# Walletv3.net
KiCad netlist of a schematic drawn in EAGLE
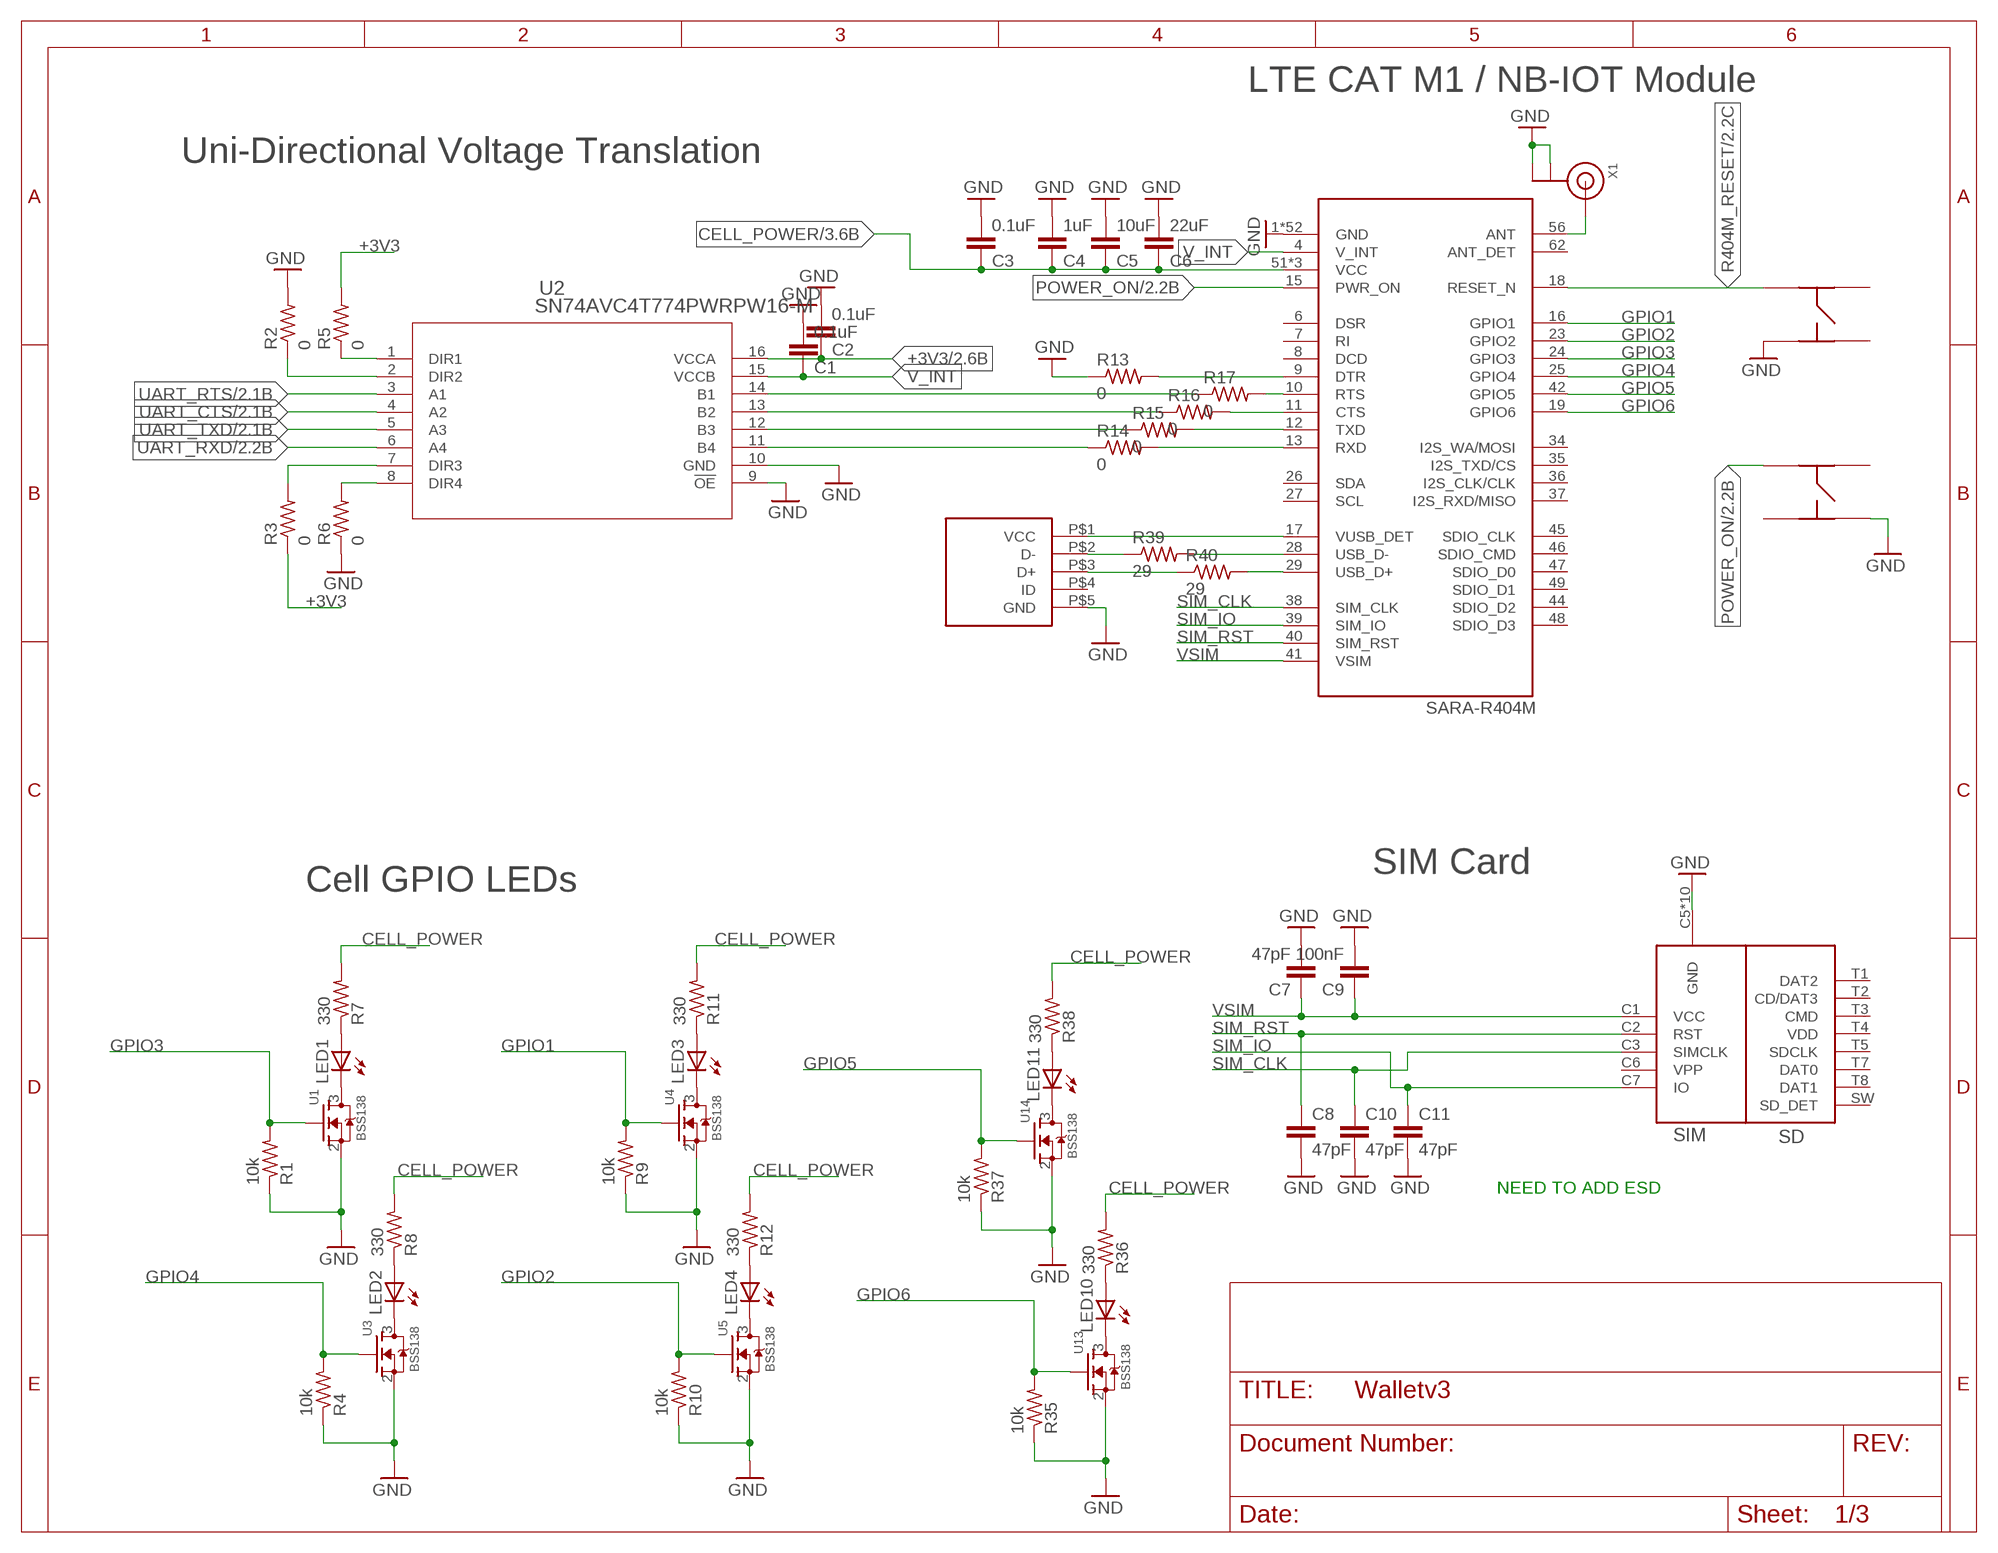
[diagram p0: schematic, sheet 1]
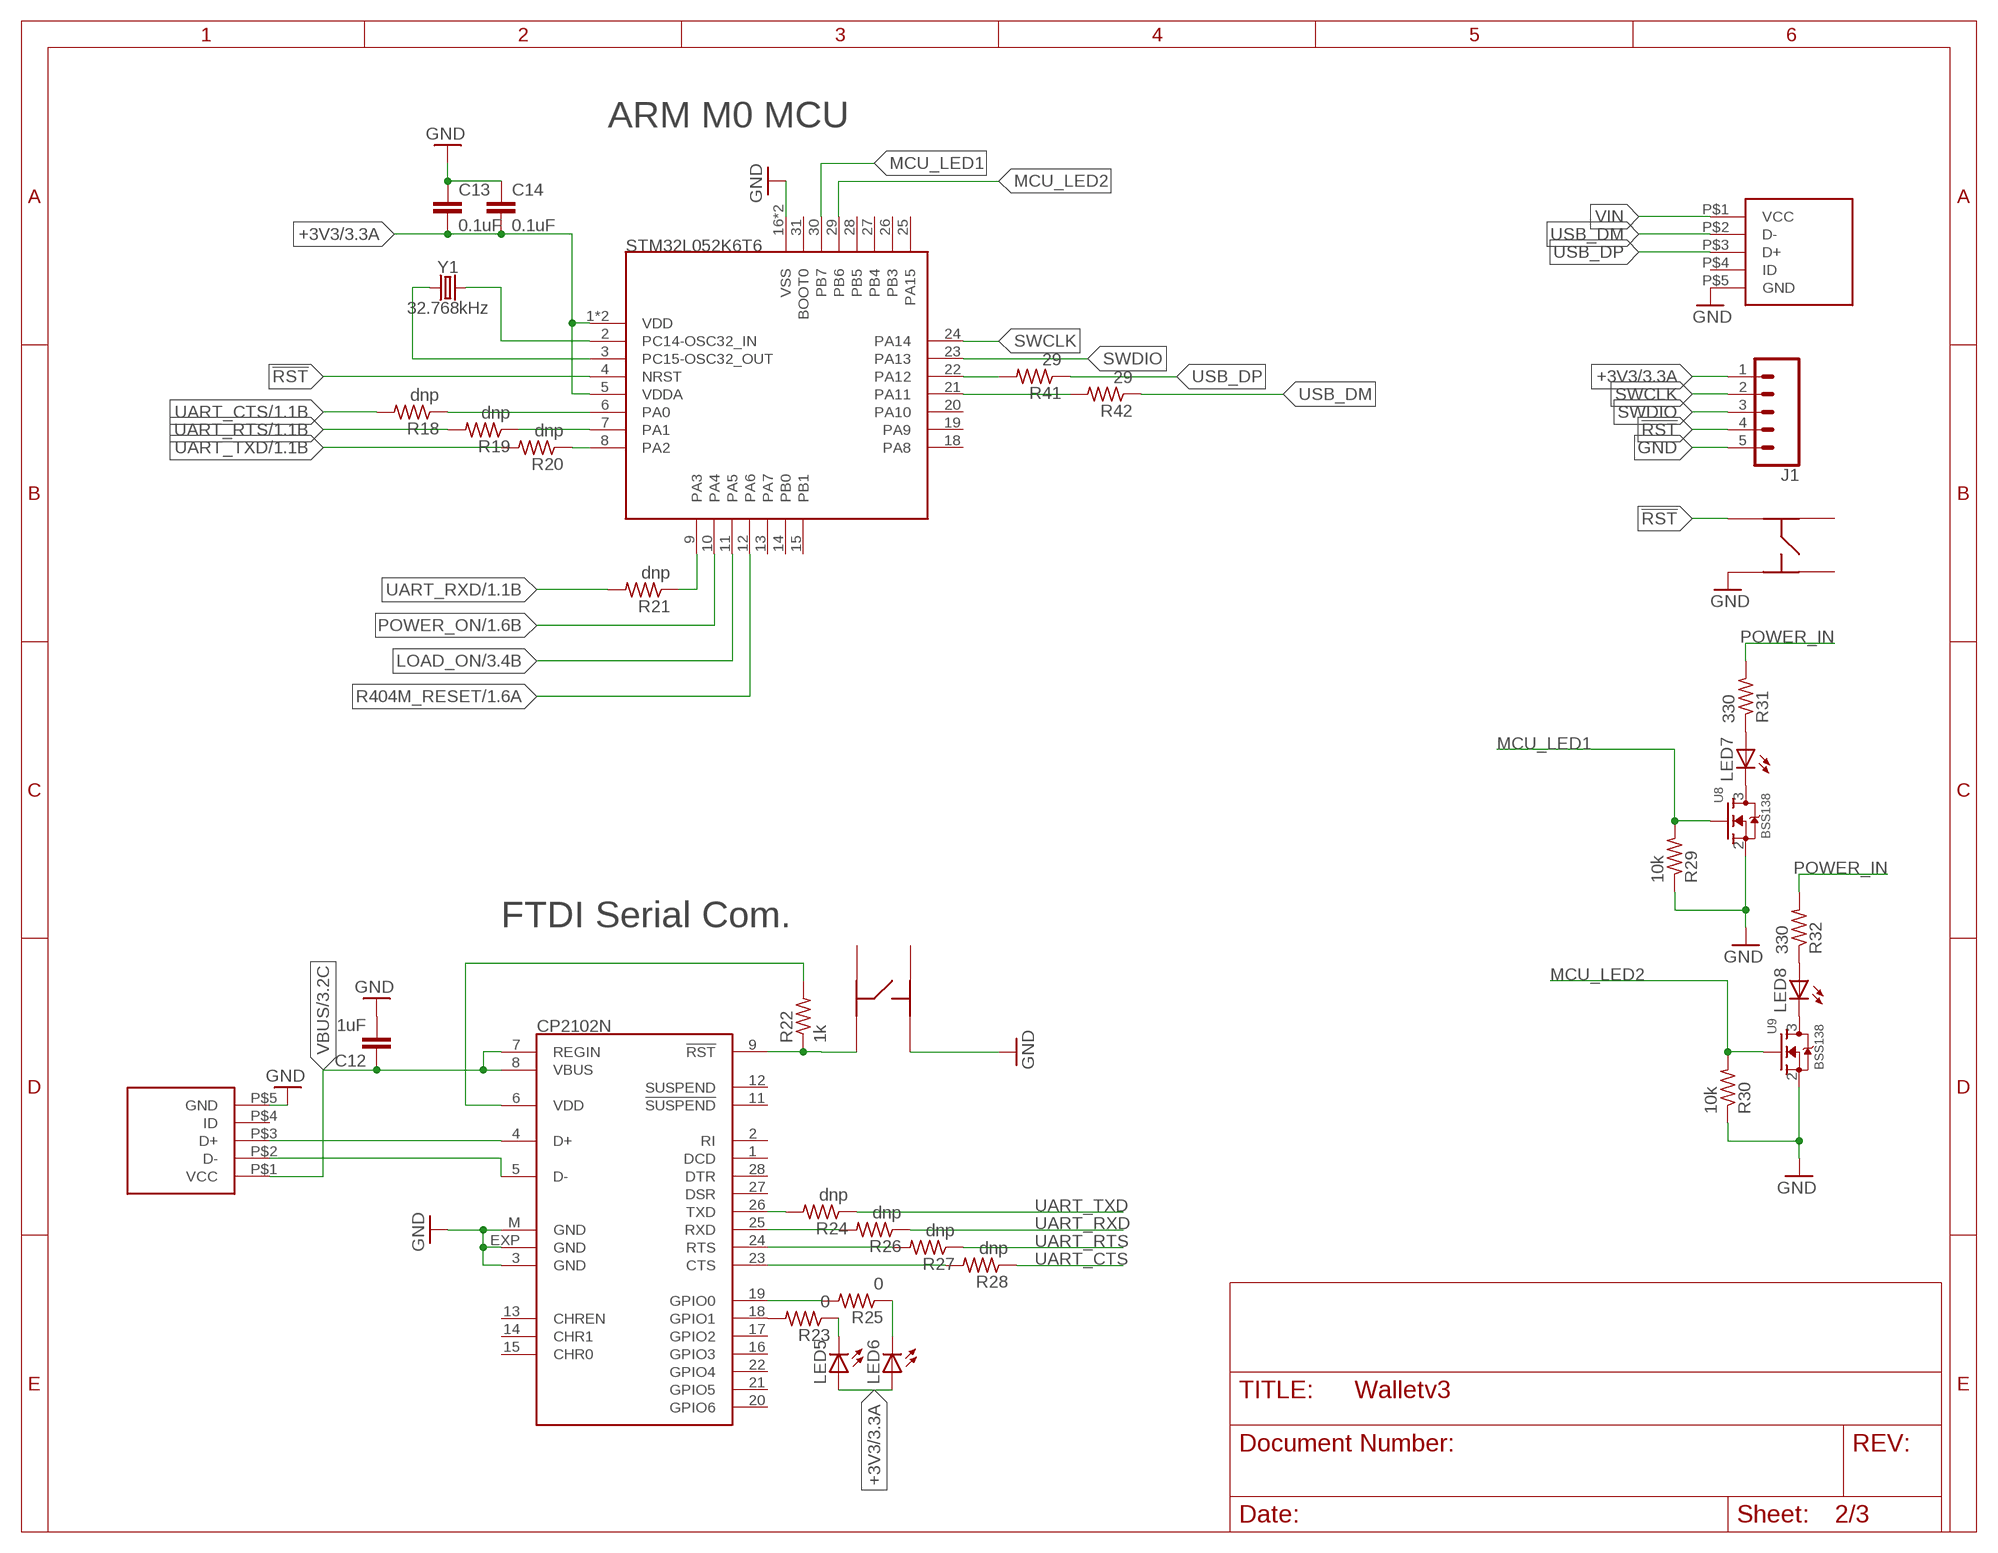
[diagram p1: schematic, sheet 2]
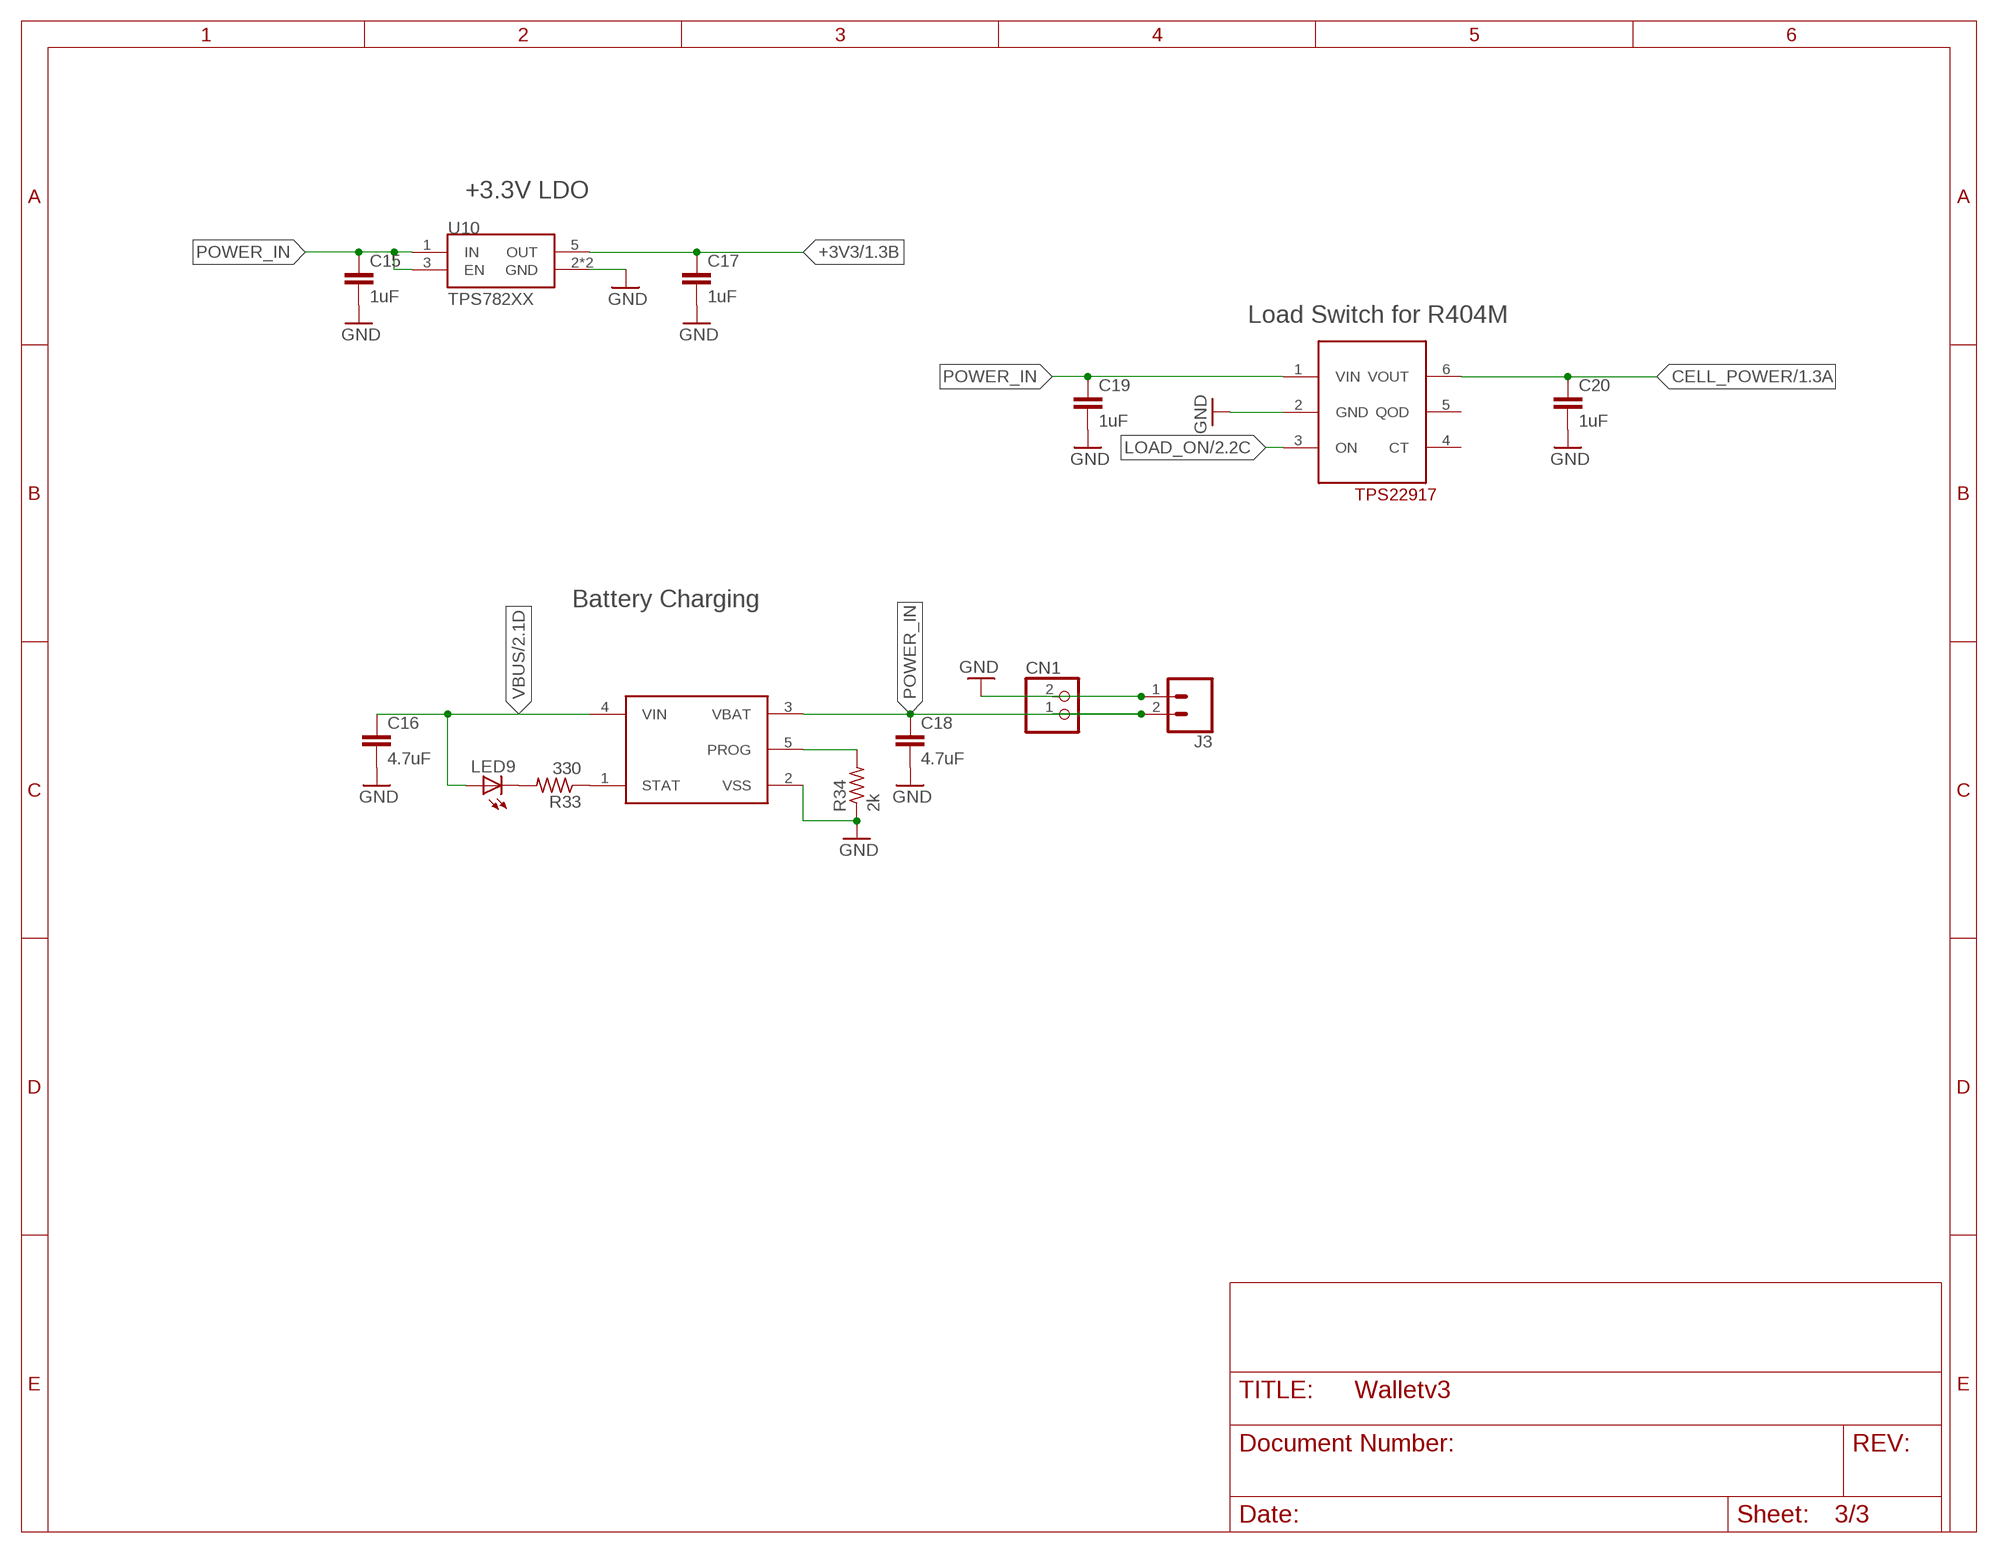
[diagram p2: schematic, sheet 3]

(export (version "E")
  (design (tool "Eeschema 10.0.6"))
  (components
    (comp (ref "C15")
      (value "1uF")
      (footprint "eagle-import:C0402")
      (libsource (lib "eagle-import") (part "C-EUC0402"))
    )
    (comp (ref "C16")
      (value "4.7uF")
      (footprint "eagle-import:C0603")
      (libsource (lib "eagle-import") (part "C-EUC0603"))
    )
    (comp (ref "C17")
      (value "1uF")
      (footprint "eagle-import:C0402")
      (libsource (lib "eagle-import") (part "C-EUC0402"))
    )
    (comp (ref "C18")
      (value "4.7uF")
      (footprint "eagle-import:C0603")
      (libsource (lib "eagle-import") (part "C-EUC0603"))
    )
    (comp (ref "C19")
      (value "1uF")
      (footprint "eagle-import:C0402")
      (libsource (lib "eagle-import") (part "C-EUC0402"))
    )
    (comp (ref "C20")
      (value "1uF")
      (footprint "eagle-import:C0402")
      (libsource (lib "eagle-import") (part "C-EUC0402"))
    )
    (comp (ref "CN1")
      (value "JST_2PIN-SMT-RA")
      (footprint "eagle-import:JST-PH-2-SMT-RA")
      (libsource (lib "eagle-import") (part "JST_2PIN-SMT-RA"))
    )
    (comp (ref "J3")
      (value "CONN_02")
      (footprint "eagle-import:1X02")
      (libsource (lib "eagle-import") (part "CONN_02"))
    )
    (comp (ref "LED9")
      (value "LEDCHIP-LED0603")
      (footprint "eagle-import:CHIP-LED0603")
      (libsource (lib "eagle-import") (part "LEDCHIP-LED0603"))
    )
    (comp (ref "R33")
      (value "330")
      (footprint "eagle-import:R0402")
      (libsource (lib "eagle-import") (part "R-US_R0402"))
    )
    (comp (ref "R34")
      (value "2k")
      (footprint "eagle-import:R0402")
      (libsource (lib "eagle-import") (part "R-US_R0402"))
    )
    (comp (ref "U10")
      (value "TPS782XX")
      (footprint "eagle-import:SOT23-5L")
      (libsource (lib "eagle-import") (part "TPS782XX"))
    )
    (comp (ref "U11")
      (value "MCP73831")
      (footprint "eagle-import:SOT23-5L")
      (libsource (lib "eagle-import") (part "MCP73831"))
    )
    (comp (ref "U12")
      (value "TPS22917")
      (footprint "eagle-import:SOT23-6")
      (libsource (lib "eagle-import") (part "TPS22917"))
    )
    (comp (ref "C12")
      (value "1uF")
      (footprint "eagle-import:C0402")
      (libsource (lib "eagle-import") (part "C-EUC0402"))
    )
    (comp (ref "C13")
      (value "0.1uF")
      (footprint "eagle-import:C0402")
      (libsource (lib "eagle-import") (part "C-EUC0402"))
    )
    (comp (ref "C14")
      (value "0.1uF")
      (footprint "eagle-import:C0402")
      (libsource (lib "eagle-import") (part "C-EUC0402"))
    )
    (comp (ref "IC1")
      (value "CP2102")
      (footprint "eagle-import:MLP28")
      (fields (field (name "MF") "FARNELL") (field (name "MPN") "CP2102-GM"))
      (libsource (lib "eagle-import") (part "CP2102"))
    )
    (comp (ref "J1")
      (value "CONN_05")
      (footprint "eagle-import:1X05")
      (libsource (lib "eagle-import") (part "CONN_05"))
    )
    (comp (ref "LED5")
      (value "LEDCHIPLED_0603")
      (footprint "eagle-import:CHIPLED_0603")
      (libsource (lib "eagle-import") (part "LEDCHIPLED_0603"))
    )
    (comp (ref "LED6")
      (value "LEDCHIPLED_0603")
      (footprint "eagle-import:CHIPLED_0603")
      (libsource (lib "eagle-import") (part "LEDCHIPLED_0603"))
    )
    (comp (ref "LED7")
      (value "LEDCHIPLED_0603")
      (footprint "eagle-import:CHIPLED_0603")
      (libsource (lib "eagle-import") (part "LEDCHIPLED_0603"))
    )
    (comp (ref "LED8")
      (value "LEDCHIPLED_0603")
      (footprint "eagle-import:CHIPLED_0603")
      (libsource (lib "eagle-import") (part "LEDCHIPLED_0603"))
    )
    (comp (ref "R18")
      (value "dnp")
      (footprint "eagle-import:R0402")
      (libsource (lib "eagle-import") (part "R-US_R0402"))
    )
    (comp (ref "R19")
      (value "dnp")
      (footprint "eagle-import:R0402")
      (libsource (lib "eagle-import") (part "R-US_R0402"))
    )
    (comp (ref "R20")
      (value "dnp")
      (footprint "eagle-import:R0402")
      (libsource (lib "eagle-import") (part "R-US_R0402"))
    )
    (comp (ref "R21")
      (value "dnp")
      (footprint "eagle-import:R0402")
      (libsource (lib "eagle-import") (part "R-US_R0402"))
    )
    (comp (ref "R22")
      (value "1k")
      (footprint "eagle-import:R0402")
      (libsource (lib "eagle-import") (part "R-US_R0402"))
    )
    (comp (ref "R23")
      (value "0")
      (footprint "eagle-import:R0402")
      (libsource (lib "eagle-import") (part "R-US_R0402"))
    )
    (comp (ref "R24")
      (value "dnp")
      (footprint "eagle-import:R0402")
      (libsource (lib "eagle-import") (part "R-US_R0402"))
    )
    (comp (ref "R25")
      (value "0")
      (footprint "eagle-import:R0402")
      (libsource (lib "eagle-import") (part "R-US_R0402"))
    )
    (comp (ref "R26")
      (value "dnp")
      (footprint "eagle-import:R0402")
      (libsource (lib "eagle-import") (part "R-US_R0402"))
    )
    (comp (ref "R27")
      (value "dnp")
      (footprint "eagle-import:R0402")
      (libsource (lib "eagle-import") (part "R-US_R0402"))
    )
    (comp (ref "R28")
      (value "dnp")
      (footprint "eagle-import:R0402")
      (libsource (lib "eagle-import") (part "R-US_R0402"))
    )
    (comp (ref "R29")
      (value "10k")
      (footprint "eagle-import:R0402")
      (libsource (lib "eagle-import") (part "R-US_R0402"))
    )
    (comp (ref "R30")
      (value "10k")
      (footprint "eagle-import:R0402")
      (libsource (lib "eagle-import") (part "R-US_R0402"))
    )
    (comp (ref "R31")
      (value "330")
      (footprint "eagle-import:R0402")
      (libsource (lib "eagle-import") (part "R-US_R0402"))
    )
    (comp (ref "R32")
      (value "330")
      (footprint "eagle-import:R0402")
      (libsource (lib "eagle-import") (part "R-US_R0402"))
    )
    (comp (ref "R41")
      (value "29")
      (footprint "eagle-import:R0402")
      (libsource (lib "eagle-import") (part "R-US_R0402"))
    )
    (comp (ref "R42")
      (value "29")
      (footprint "eagle-import:R0402")
      (libsource (lib "eagle-import") (part "R-US_R0402"))
    )
    (comp (ref "S3")
      (value "KMR731NG")
      (footprint "eagle-import:KMR731NG")
      (libsource (lib "eagle-import") (part "KMR731NG"))
    )
    (comp (ref "S4")
      (value "KMR731NG")
      (footprint "eagle-import:KMR731NG")
      (libsource (lib "eagle-import") (part "KMR731NG"))
    )
    (comp (ref "U$3")
      (value "MICRO_USB")
      (footprint "eagle-import:MOLEX_USB")
      (libsource (lib "eagle-import") (part "MICRO_USB"))
    )
    (comp (ref "U$4")
      (value "MICRO_USB")
      (footprint "eagle-import:MOLEX_USB")
      (libsource (lib "eagle-import") (part "MICRO_USB"))
    )
    (comp (ref "U7")
      (value "STM32L052K6T6LQFP32-7X7")
      (footprint "eagle-import:QFP80P900X900X160-32")
      (libsource (lib "eagle-import") (part "STM32L052K6T6LQFP32-7X7"))
    )
    (comp (ref "U8")
      (value "BSS138")
      (footprint "eagle-import:SOT23-3")
      (libsource (lib "eagle-import") (part "BSS138"))
    )
    (comp (ref "U9")
      (value "BSS138")
      (footprint "eagle-import:SOT23-3")
      (libsource (lib "eagle-import") (part "BSS138"))
    )
    (comp (ref "Y1")
      (value "32.768kHz")
      (footprint "eagle-import:CRYSTAL-SMD-3.2X1.5MM")
      (libsource (lib "eagle-import") (part "CRYSTAL-32.768KHZSMD-3.2X1.5"))
    )
    (comp (ref "C1")
      (value "0.1uF")
      (footprint "eagle-import:C0402")
      (libsource (lib "eagle-import") (part "C-EUC0402"))
    )
    (comp (ref "C2")
      (value "0.1uF")
      (footprint "eagle-import:C0402")
      (libsource (lib "eagle-import") (part "C-EUC0402"))
    )
    (comp (ref "C3")
      (value "0.1uF")
      (footprint "eagle-import:C0402")
      (libsource (lib "eagle-import") (part "C-EUC0402"))
    )
    (comp (ref "C4")
      (value "1uF")
      (footprint "eagle-import:C0402")
      (libsource (lib "eagle-import") (part "C-EUC0402"))
    )
    (comp (ref "C5")
      (value "10uF")
      (footprint "eagle-import:C0603")
      (libsource (lib "eagle-import") (part "C-EUC0603"))
    )
    (comp (ref "C6")
      (value "22uF")
      (footprint "eagle-import:C0805")
      (libsource (lib "eagle-import") (part "C-EUC0805"))
    )
    (comp (ref "C7")
      (value "47pF")
      (footprint "eagle-import:C0402")
      (libsource (lib "eagle-import") (part "C-EUC0402"))
    )
    (comp (ref "C8")
      (value "47pF")
      (footprint "eagle-import:C0402")
      (libsource (lib "eagle-import") (part "C-EUC0402"))
    )
    (comp (ref "C9")
      (value "100nF")
      (footprint "eagle-import:C0402")
      (libsource (lib "eagle-import") (part "C-EUC0402"))
    )
    (comp (ref "C10")
      (value "47pF")
      (footprint "eagle-import:C0402")
      (libsource (lib "eagle-import") (part "C-EUC0402"))
    )
    (comp (ref "C11")
      (value "47pF")
      (footprint "eagle-import:C0402")
      (libsource (lib "eagle-import") (part "C-EUC0402"))
    )
    (comp (ref "LED1")
      (value "LEDCHIPLED_0603")
      (footprint "eagle-import:CHIPLED_0603")
      (libsource (lib "eagle-import") (part "LEDCHIPLED_0603"))
    )
    (comp (ref "LED2")
      (value "LEDCHIPLED_0603")
      (footprint "eagle-import:CHIPLED_0603")
      (libsource (lib "eagle-import") (part "LEDCHIPLED_0603"))
    )
    (comp (ref "LED3")
      (value "LEDCHIPLED_0603")
      (footprint "eagle-import:CHIPLED_0603")
      (libsource (lib "eagle-import") (part "LEDCHIPLED_0603"))
    )
    (comp (ref "LED4")
      (value "LEDCHIPLED_0603")
      (footprint "eagle-import:CHIPLED_0603")
      (libsource (lib "eagle-import") (part "LEDCHIPLED_0603"))
    )
    (comp (ref "LED10")
      (value "LEDCHIPLED_0603")
      (footprint "eagle-import:CHIPLED_0603")
      (libsource (lib "eagle-import") (part "LEDCHIPLED_0603"))
    )
    (comp (ref "LED11")
      (value "LEDCHIPLED_0603")
      (footprint "eagle-import:CHIPLED_0603")
      (libsource (lib "eagle-import") (part "LEDCHIPLED_0603"))
    )
    (comp (ref "R1")
      (value "10k")
      (footprint "eagle-import:R0402")
      (libsource (lib "eagle-import") (part "R-US_R0402"))
    )
    (comp (ref "R2")
      (value "0")
      (footprint "eagle-import:R0402")
      (libsource (lib "eagle-import") (part "R-US_R0402"))
    )
    (comp (ref "R3")
      (value "0")
      (footprint "eagle-import:R0402")
      (libsource (lib "eagle-import") (part "R-US_R0402"))
    )
    (comp (ref "R4")
      (value "10k")
      (footprint "eagle-import:R0402")
      (libsource (lib "eagle-import") (part "R-US_R0402"))
    )
    (comp (ref "R5")
      (value "0")
      (footprint "eagle-import:R0402")
      (libsource (lib "eagle-import") (part "R-US_R0402"))
    )
    (comp (ref "R6")
      (value "0")
      (footprint "eagle-import:R0402")
      (libsource (lib "eagle-import") (part "R-US_R0402"))
    )
    (comp (ref "R7")
      (value "330")
      (footprint "eagle-import:R0402")
      (libsource (lib "eagle-import") (part "R-US_R0402"))
    )
    (comp (ref "R8")
      (value "330")
      (footprint "eagle-import:R0402")
      (libsource (lib "eagle-import") (part "R-US_R0402"))
    )
    (comp (ref "R9")
      (value "10k")
      (footprint "eagle-import:R0402")
      (libsource (lib "eagle-import") (part "R-US_R0402"))
    )
    (comp (ref "R10")
      (value "10k")
      (footprint "eagle-import:R0402")
      (libsource (lib "eagle-import") (part "R-US_R0402"))
    )
    (comp (ref "R11")
      (value "330")
      (footprint "eagle-import:R0402")
      (libsource (lib "eagle-import") (part "R-US_R0402"))
    )
    (comp (ref "R12")
      (value "330")
      (footprint "eagle-import:R0402")
      (libsource (lib "eagle-import") (part "R-US_R0402"))
    )
    (comp (ref "R13")
      (value "0")
      (footprint "eagle-import:R0402")
      (libsource (lib "eagle-import") (part "R-US_R0402"))
    )
    (comp (ref "R14")
      (value "0")
      (footprint "eagle-import:R0402")
      (libsource (lib "eagle-import") (part "R-US_R0402"))
    )
    (comp (ref "R15")
      (value "0")
      (footprint "eagle-import:R0402")
      (libsource (lib "eagle-import") (part "R-US_R0402"))
    )
    (comp (ref "R16")
      (value "0")
      (footprint "eagle-import:R0402")
      (libsource (lib "eagle-import") (part "R-US_R0402"))
    )
    (comp (ref "R17")
      (value "0")
      (footprint "eagle-import:R0402")
      (libsource (lib "eagle-import") (part "R-US_R0402"))
    )
    (comp (ref "R35")
      (value "10k")
      (footprint "eagle-import:R0402")
      (libsource (lib "eagle-import") (part "R-US_R0402"))
    )
    (comp (ref "R36")
      (value "330")
      (footprint "eagle-import:R0402")
      (libsource (lib "eagle-import") (part "R-US_R0402"))
    )
    (comp (ref "R37")
      (value "10k")
      (footprint "eagle-import:R0402")
      (libsource (lib "eagle-import") (part "R-US_R0402"))
    )
    (comp (ref "R38")
      (value "330")
      (footprint "eagle-import:R0402")
      (libsource (lib "eagle-import") (part "R-US_R0402"))
    )
    (comp (ref "R39")
      (value "29")
      (footprint "eagle-import:R0402")
      (libsource (lib "eagle-import") (part "R-US_R0402"))
    )
    (comp (ref "R40")
      (value "29")
      (footprint "eagle-import:R0402")
      (libsource (lib "eagle-import") (part "R-US_R0402"))
    )
    (comp (ref "S1")
      (value "KMR731NG")
      (footprint "eagle-import:KMR731NG")
      (libsource (lib "eagle-import") (part "KMR731NG"))
    )
    (comp (ref "S2")
      (value "KMR731NG")
      (footprint "eagle-import:KMR731NG")
      (libsource (lib "eagle-import") (part "KMR731NG"))
    )
    (comp (ref "U$1")
      (value "SIM_SD_MOLEX")
      (footprint "eagle-import:SIM_SD_MOLEX")
      (libsource (lib "eagle-import") (part "SIM_SD_MOLEX"))
    )
    (comp (ref "U$2")
      (value "MICRO_USB")
      (footprint "eagle-import:MOLEX_USB")
      (libsource (lib "eagle-import") (part "MICRO_USB"))
    )
    (comp (ref "U1")
      (value "BSS138")
      (footprint "eagle-import:SOT23-3")
      (libsource (lib "eagle-import") (part "BSS138"))
    )
    (comp (ref "U2")
      (value "SN74AVC4T774PWRPW16-M")
      (footprint "eagle-import:PW16-M")
      (fields (field (name "MANUFACTURER_PART_NUMBER") "SN74AVC4T774PWR"))
      (libsource (lib "eagle-import") (part "SN74AVC4T774PWRPW16-M"))
    )
    (comp (ref "U3")
      (value "BSS138")
      (footprint "eagle-import:SOT23-3")
      (libsource (lib "eagle-import") (part "BSS138"))
    )
    (comp (ref "U4")
      (value "BSS138")
      (footprint "eagle-import:SOT23-3")
      (libsource (lib "eagle-import") (part "BSS138"))
    )
    (comp (ref "U5")
      (value "BSS138")
      (footprint "eagle-import:SOT23-3")
      (libsource (lib "eagle-import") (part "BSS138"))
    )
    (comp (ref "U6")
      (value "SARA-R404M")
      (footprint "eagle-import:SARA-R404M")
      (libsource (lib "eagle-import") (part "SARA-R404M"))
    )
    (comp (ref "U13")
      (value "BSS138")
      (footprint "eagle-import:SOT23-3")
      (libsource (lib "eagle-import") (part "BSS138"))
    )
    (comp (ref "U14")
      (value "BSS138")
      (footprint "eagle-import:SOT23-3")
      (libsource (lib "eagle-import") (part "BSS138"))
    )
    (comp (ref "X1")
      (value "ANTENNA_U.FL")
      (footprint "eagle-import:U.FL")
      (libsource (lib "eagle-import") (part "ANTENNA_U.FL"))
    )
  )
  (nets
    (net (code "1") (name "+3V3") (class "Default")
      (node (ref "C13") (pin "2") (pinfunction "2_2") (pintype "passive"))
      (node (ref "C14") (pin "2") (pinfunction "2_2") (pintype "passive"))
      (node (ref "C17") (pin "1") (pinfunction "1_1") (pintype "passive"))
      (node (ref "C2") (pin "1") (pinfunction "1_1") (pintype "passive"))
      (node (ref "J1") (pin "1") (pinfunction "1_1") (pintype "passive"))
      (node (ref "LED5") (pin "A") (pinfunction "A_A") (pintype "passive"))
      (node (ref "LED6") (pin "A") (pinfunction "A_A") (pintype "passive"))
      (node (ref "R3") (pin "1") (pinfunction "1_1") (pintype "passive"))
      (node (ref "R5") (pin "2") (pinfunction "2_2") (pintype "passive"))
      (node (ref "U10") (pin "5") (pinfunction "OUT_5") (pintype "bidirectional"))
      (node (ref "U2") (pin "16") (pinfunction "VCCA_16") (pintype "power_in"))
      (node (ref "U7") (pin "1") (pinfunction "VDD_1") (pintype "bidirectional"))
      (node (ref "U7") (pin "17") (pinfunction "VDD_17") (pintype "bidirectional"))
      (node (ref "U7") (pin "5") (pinfunction "VDDA_5") (pintype "bidirectional"))
    )
    (net (code "2") (name "CELL_POWER") (class "Default")
      (node (ref "C20") (pin "1") (pinfunction "1_1") (pintype "passive"))
      (node (ref "C3") (pin "1") (pinfunction "1_1") (pintype "passive"))
      (node (ref "C4") (pin "1") (pinfunction "1_1") (pintype "passive"))
      (node (ref "C5") (pin "1") (pinfunction "1_1") (pintype "passive"))
      (node (ref "C6") (pin "1") (pinfunction "1_1") (pintype "passive"))
      (node (ref "R11") (pin "2") (pinfunction "2_2") (pintype "passive"))
      (node (ref "R12") (pin "2") (pinfunction "2_2") (pintype "passive"))
      (node (ref "R36") (pin "2") (pinfunction "2_2") (pintype "passive"))
      (node (ref "R38") (pin "2") (pinfunction "2_2") (pintype "passive"))
      (node (ref "R7") (pin "2") (pinfunction "2_2") (pintype "passive"))
      (node (ref "R8") (pin "2") (pinfunction "2_2") (pintype "passive"))
      (node (ref "U12") (pin "6") (pinfunction "VOUT_6") (pintype "bidirectional"))
      (node (ref "U6") (pin "51") (pinfunction "VCC_51") (pintype "bidirectional"))
      (node (ref "U6") (pin "52") (pinfunction "VCC_52") (pintype "bidirectional"))
      (node (ref "U6") (pin "53") (pinfunction "VCC_53") (pintype "bidirectional"))
    )
    (net (code "3") (name "GND") (class "Default")
      (node (ref "C1") (pin "2") (pinfunction "2_2") (pintype "passive"))
      (node (ref "C10") (pin "2") (pinfunction "2_2") (pintype "passive"))
      (node (ref "C11") (pin "2") (pinfunction "2_2") (pintype "passive"))
      (node (ref "C12") (pin "2") (pinfunction "2_2") (pintype "passive"))
      (node (ref "C13") (pin "1") (pinfunction "1_1") (pintype "passive"))
      (node (ref "C14") (pin "1") (pinfunction "1_1") (pintype "passive"))
      (node (ref "C15") (pin "2") (pinfunction "2_2") (pintype "passive"))
      (node (ref "C16") (pin "2") (pinfunction "2_2") (pintype "passive"))
      (node (ref "C17") (pin "2") (pinfunction "2_2") (pintype "passive"))
      (node (ref "C18") (pin "2") (pinfunction "2_2") (pintype "passive"))
      (node (ref "C19") (pin "2") (pinfunction "2_2") (pintype "passive"))
      (node (ref "C2") (pin "2") (pinfunction "2_2") (pintype "passive"))
      (node (ref "C20") (pin "2") (pinfunction "2_2") (pintype "passive"))
      (node (ref "C3") (pin "2") (pinfunction "2_2") (pintype "passive"))
      (node (ref "C4") (pin "2") (pinfunction "2_2") (pintype "passive"))
      (node (ref "C5") (pin "2") (pinfunction "2_2") (pintype "passive"))
      (node (ref "C6") (pin "2") (pinfunction "2_2") (pintype "passive"))
      (node (ref "C7") (pin "2") (pinfunction "2_2") (pintype "passive"))
      (node (ref "C8") (pin "2") (pinfunction "2_2") (pintype "passive"))
      (node (ref "C9") (pin "2") (pinfunction "2_2") (pintype "passive"))
      (node (ref "CN1") (pin "2") (pinfunction "1_2") (pintype "passive"))
      (node (ref "IC1") (pin "3") (pinfunction "GND_3") (pintype "power_in"))
      (node (ref "IC1") (pin "EXP") (pinfunction "GND_EXP") (pintype "power_in"))
      (node (ref "IC1") (pin "M") (pinfunction "GND_M") (pintype "power_in"))
      (node (ref "J1") (pin "5") (pinfunction "5_5") (pintype "passive"))
      (node (ref "J3") (pin "1") (pinfunction "1_1") (pintype "passive"))
      (node (ref "R1") (pin "1") (pinfunction "1_1") (pintype "passive"))
      (node (ref "R10") (pin "1") (pinfunction "1_1") (pintype "passive"))
      (node (ref "R13") (pin "1") (pinfunction "1_1") (pintype "passive"))
      (node (ref "R2") (pin "2") (pinfunction "2_2") (pintype "passive"))
      (node (ref "R29") (pin "1") (pinfunction "1_1") (pintype "passive"))
      (node (ref "R30") (pin "1") (pinfunction "1_1") (pintype "passive"))
      (node (ref "R34") (pin "1") (pinfunction "1_1") (pintype "passive"))
      (node (ref "R35") (pin "1") (pinfunction "1_1") (pintype "passive"))
      (node (ref "R37") (pin "1") (pinfunction "1_1") (pintype "passive"))
      (node (ref "R4") (pin "1") (pinfunction "1_1") (pintype "passive"))
      (node (ref "R6") (pin "1") (pinfunction "1_1") (pintype "passive"))
      (node (ref "R9") (pin "1") (pinfunction "1_1") (pintype "passive"))
      (node (ref "S1") (pin "P$4") (pinfunction "P$4_P$4") (pintype "bidirectional"))
      (node (ref "S2") (pin "P$3") (pinfunction "P$3_P$3") (pintype "bidirectional"))
      (node (ref "S3") (pin "P$4") (pinfunction "P$4_P$4") (pintype "bidirectional"))
      (node (ref "S4") (pin "P$4") (pinfunction "P$4_P$4") (pintype "bidirectional"))
      (node (ref "U$1") (pin "C5") (pinfunction "GND_C5") (pintype "bidirectional"))
      (node (ref "U$1") (pin "G1") (pinfunction "GND_G1") (pintype "bidirectional"))
      (node (ref "U$1") (pin "G2") (pinfunction "GND_G2") (pintype "bidirectional"))
      (node (ref "U$1") (pin "G3") (pinfunction "GND_G3") (pintype "bidirectional"))
      (node (ref "U$1") (pin "G4") (pinfunction "GND_G4") (pintype "bidirectional"))
      (node (ref "U$1") (pin "G5") (pinfunction "GND_G5") (pintype "bidirectional"))
      (node (ref "U$1") (pin "G6") (pinfunction "GND_G6") (pintype "bidirectional"))
      (node (ref "U$1") (pin "G7") (pinfunction "GND_G7") (pintype "bidirectional"))
      (node (ref "U$1") (pin "G8") (pinfunction "GND_G8") (pintype "bidirectional"))
      (node (ref "U$1") (pin "T6") (pinfunction "GND_T6") (pintype "bidirectional"))
      (node (ref "U$2") (pin "P$5") (pinfunction "GND_P$5") (pintype "bidirectional"))
      (node (ref "U$3") (pin "P$5") (pinfunction "GND_P$5") (pintype "bidirectional"))
      (node (ref "U$4") (pin "P$5") (pinfunction "GND_P$5") (pintype "bidirectional"))
      (node (ref "U1") (pin "2") (pinfunction "S_2") (pintype "bidirectional"))
      (node (ref "U10") (pin "2") (pinfunction "GND_2") (pintype "bidirectional"))
      (node (ref "U10") (pin "4") (pinfunction "GND_4") (pintype "bidirectional"))
      (node (ref "U11") (pin "2") (pinfunction "VSS_2") (pintype "bidirectional"))
      (node (ref "U12") (pin "2") (pinfunction "GND_2") (pintype "bidirectional"))
      (node (ref "U13") (pin "2") (pinfunction "S_2") (pintype "bidirectional"))
      (node (ref "U14") (pin "2") (pinfunction "S_2") (pintype "bidirectional"))
      (node (ref "U2") (pin "10") (pinfunction "GND_10") (pintype "power_in"))
      (node (ref "U2") (pin "9") (pinfunction "~{OE}_9") (pintype "input"))
      (node (ref "U3") (pin "2") (pinfunction "S_2") (pintype "bidirectional"))
      (node (ref "U4") (pin "2") (pinfunction "S_2") (pintype "bidirectional"))
      (node (ref "U5") (pin "2") (pinfunction "S_2") (pintype "bidirectional"))
      (node (ref "U6") (pin "1") (pinfunction "GND_1") (pintype "bidirectional"))
      (node (ref "U6") (pin "14") (pinfunction "GND_14") (pintype "bidirectional"))
      (node (ref "U6") (pin "20") (pinfunction "GND_20") (pintype "bidirectional"))
      (node (ref "U6") (pin "21") (pinfunction "GND_21") (pintype "bidirectional"))
      (node (ref "U6") (pin "22") (pinfunction "GND_22") (pintype "bidirectional"))
      (node (ref "U6") (pin "3") (pinfunction "GND_3") (pintype "bidirectional"))
      (node (ref "U6") (pin "30") (pinfunction "GND_30") (pintype "bidirectional"))
      (node (ref "U6") (pin "32") (pinfunction "GND_32") (pintype "bidirectional"))
      (node (ref "U6") (pin "43") (pinfunction "GND_43") (pintype "bidirectional"))
      (node (ref "U6") (pin "5") (pinfunction "GND_5") (pintype "bidirectional"))
      (node (ref "U6") (pin "50") (pinfunction "GND_50") (pintype "bidirectional"))
      (node (ref "U6") (pin "54") (pinfunction "GND_54") (pintype "bidirectional"))
      (node (ref "U6") (pin "55") (pinfunction "GND_55") (pintype "bidirectional"))
      (node (ref "U6") (pin "57") (pinfunction "GND_57") (pintype "bidirectional"))
      (node (ref "U6") (pin "58") (pinfunction "GND_58") (pintype "bidirectional"))
      (node (ref "U6") (pin "59") (pinfunction "GND_59") (pintype "bidirectional"))
      (node (ref "U6") (pin "60") (pinfunction "GND_60") (pintype "bidirectional"))
      (node (ref "U6") (pin "61") (pinfunction "GND_61") (pintype "bidirectional"))
      (node (ref "U6") (pin "63") (pinfunction "GND_63") (pintype "bidirectional"))
      (node (ref "U6") (pin "64") (pinfunction "GND_64") (pintype "bidirectional"))
      (node (ref "U6") (pin "65") (pinfunction "GND_65") (pintype "bidirectional"))
      (node (ref "U6") (pin "66") (pinfunction "GND_66") (pintype "bidirectional"))
      (node (ref "U6") (pin "67") (pinfunction "GND_67") (pintype "bidirectional"))
      (node (ref "U6") (pin "68") (pinfunction "GND_68") (pintype "bidirectional"))
      (node (ref "U6") (pin "69") (pinfunction "GND_69") (pintype "bidirectional"))
      (node (ref "U6") (pin "70") (pinfunction "GND_70") (pintype "bidirectional"))
      (node (ref "U6") (pin "71") (pinfunction "GND_71") (pintype "bidirectional"))
      (node (ref "U6") (pin "72") (pinfunction "GND_72") (pintype "bidirectional"))
      (node (ref "U6") (pin "73") (pinfunction "GND_73") (pintype "bidirectional"))
      (node (ref "U6") (pin "74") (pinfunction "GND_74") (pintype "bidirectional"))
      (node (ref "U6") (pin "75") (pinfunction "GND_75") (pintype "bidirectional"))
      (node (ref "U6") (pin "76") (pinfunction "GND_76") (pintype "bidirectional"))
      (node (ref "U6") (pin "77") (pinfunction "GND_77") (pintype "bidirectional"))
      (node (ref "U6") (pin "78") (pinfunction "GND_78") (pintype "bidirectional"))
      (node (ref "U6") (pin "79") (pinfunction "GND_79") (pintype "bidirectional"))
      (node (ref "U6") (pin "80") (pinfunction "GND_80") (pintype "bidirectional"))
      (node (ref "U6") (pin "81") (pinfunction "GND_81") (pintype "bidirectional"))
      (node (ref "U6") (pin "82") (pinfunction "GND_82") (pintype "bidirectional"))
      (node (ref "U6") (pin "83") (pinfunction "GND_83") (pintype "bidirectional"))
      (node (ref "U6") (pin "84") (pinfunction "GND_84") (pintype "bidirectional"))
      (node (ref "U6") (pin "85") (pinfunction "GND_85") (pintype "bidirectional"))
      (node (ref "U6") (pin "86") (pinfunction "GND_86") (pintype "bidirectional"))
      (node (ref "U6") (pin "87") (pinfunction "GND_87") (pintype "bidirectional"))
      (node (ref "U6") (pin "88") (pinfunction "GND_88") (pintype "bidirectional"))
      (node (ref "U6") (pin "89") (pinfunction "GND_89") (pintype "bidirectional"))
      (node (ref "U6") (pin "90") (pinfunction "GND_90") (pintype "bidirectional"))
      (node (ref "U6") (pin "91") (pinfunction "GND_91") (pintype "bidirectional"))
      (node (ref "U6") (pin "92") (pinfunction "GND_92") (pintype "bidirectional"))
      (node (ref "U6") (pin "93") (pinfunction "GND_93") (pintype "bidirectional"))
      (node (ref "U6") (pin "94") (pinfunction "GND_94") (pintype "bidirectional"))
      (node (ref "U6") (pin "95") (pinfunction "GND_95") (pintype "bidirectional"))
      (node (ref "U6") (pin "96") (pinfunction "GND_96") (pintype "bidirectional"))
      (node (ref "U7") (pin "16") (pinfunction "VSS_16") (pintype "bidirectional"))
      (node (ref "U7") (pin "32") (pinfunction "VSS_32") (pintype "bidirectional"))
      (node (ref "U8") (pin "2") (pinfunction "S_2") (pintype "bidirectional"))
      (node (ref "U9") (pin "2") (pinfunction "S_2") (pintype "bidirectional"))
      (node (ref "X1") (pin "1") (pinfunction "GND_1") (pintype "passive"))
      (node (ref "X1") (pin "2") (pinfunction "GND_2") (pintype "passive"))
    )
    (net (code "4") (name "GPIO1") (class "Default")
      (node (ref "R9") (pin "2") (pinfunction "2_2") (pintype "passive"))
      (node (ref "U4") (pin "1") (pinfunction "G_1") (pintype "bidirectional"))
      (node (ref "U6") (pin "16") (pinfunction "GPIO1_16") (pintype "bidirectional"))
    )
    (net (code "5") (name "GPIO2") (class "Default")
      (node (ref "R10") (pin "2") (pinfunction "2_2") (pintype "passive"))
      (node (ref "U5") (pin "1") (pinfunction "G_1") (pintype "bidirectional"))
      (node (ref "U6") (pin "23") (pinfunction "GPIO2_23") (pintype "bidirectional"))
    )
    (net (code "6") (name "GPIO3") (class "Default")
      (node (ref "R1") (pin "2") (pinfunction "2_2") (pintype "passive"))
      (node (ref "U1") (pin "1") (pinfunction "G_1") (pintype "bidirectional"))
      (node (ref "U6") (pin "24") (pinfunction "GPIO3_24") (pintype "bidirectional"))
    )
    (net (code "7") (name "GPIO4") (class "Default")
      (node (ref "R4") (pin "2") (pinfunction "2_2") (pintype "passive"))
      (node (ref "U3") (pin "1") (pinfunction "G_1") (pintype "bidirectional"))
      (node (ref "U6") (pin "25") (pinfunction "GPIO4_25") (pintype "bidirectional"))
    )
    (net (code "8") (name "GPIO5") (class "Default")
      (node (ref "R37") (pin "2") (pinfunction "2_2") (pintype "passive"))
      (node (ref "U14") (pin "1") (pinfunction "G_1") (pintype "bidirectional"))
      (node (ref "U6") (pin "42") (pinfunction "GPIO5_42") (pintype "bidirectional"))
    )
    (net (code "9") (name "GPIO6") (class "Default")
      (node (ref "R35") (pin "2") (pinfunction "2_2") (pintype "passive"))
      (node (ref "U13") (pin "1") (pinfunction "G_1") (pintype "bidirectional"))
      (node (ref "U6") (pin "19") (pinfunction "GPIO6_19") (pintype "bidirectional"))
    )
    (net (code "10") (name "LOAD_ON") (class "Default")
      (node (ref "U12") (pin "3") (pinfunction "ON_3") (pintype "bidirectional"))
      (node (ref "U7") (pin "11") (pinfunction "PA5_11") (pintype "bidirectional"))
    )
    (net (code "11") (name "MCU_LED1") (class "Default")
      (node (ref "R29") (pin "2") (pinfunction "2_2") (pintype "passive"))
      (node (ref "U7") (pin "30") (pinfunction "PB7_30") (pintype "bidirectional"))
      (node (ref "U8") (pin "1") (pinfunction "G_1") (pintype "bidirectional"))
    )
    (net (code "12") (name "MCU_LED2") (class "Default")
      (node (ref "R30") (pin "2") (pinfunction "2_2") (pintype "passive"))
      (node (ref "U7") (pin "29") (pinfunction "PB6_29") (pintype "bidirectional"))
      (node (ref "U9") (pin "1") (pinfunction "G_1") (pintype "bidirectional"))
    )
    (net (code "13") (name "Net-(IC1-CTS)") (class "Default")
      (node (ref "IC1") (pin "23") (pinfunction "CTS_23") (pintype "input"))
      (node (ref "R28") (pin "2") (pinfunction "2_2") (pintype "passive"))
    )
    (net (code "14") (name "Net-(IC1-D+)") (class "Default")
      (node (ref "IC1") (pin "4") (pinfunction "D+_4") (pintype "bidirectional"))
      (node (ref "U$3") (pin "P$3") (pinfunction "D+_P$3") (pintype "bidirectional"))
    )
    (net (code "15") (name "Net-(IC1-D-)") (class "Default")
      (node (ref "IC1") (pin "5") (pinfunction "D-_5") (pintype "bidirectional"))
      (node (ref "U$3") (pin "P$2") (pinfunction "D-_P$2") (pintype "bidirectional"))
    )
    (net (code "16") (name "Net-(IC1-GPIO0)") (class "Default")
      (node (ref "IC1") (pin "19") (pinfunction "GPIO0_19") (pintype "bidirectional"))
      (node (ref "R25") (pin "2") (pinfunction "2_2") (pintype "passive"))
    )
    (net (code "17") (name "Net-(IC1-GPIO1)") (class "Default")
      (node (ref "IC1") (pin "18") (pinfunction "GPIO1_18") (pintype "bidirectional"))
      (node (ref "R23") (pin "2") (pinfunction "2_2") (pintype "passive"))
    )
    (net (code "18") (name "Net-(IC1-RTS)") (class "Default")
      (node (ref "IC1") (pin "24") (pinfunction "RTS_24") (pintype "output"))
      (node (ref "R27") (pin "2") (pinfunction "2_2") (pintype "passive"))
    )
    (net (code "19") (name "Net-(IC1-RXD)") (class "Default")
      (node (ref "IC1") (pin "25") (pinfunction "RXD_25") (pintype "input"))
      (node (ref "R26") (pin "2") (pinfunction "2_2") (pintype "passive"))
    )
    (net (code "20") (name "Net-(IC1-TXD)") (class "Default")
      (node (ref "IC1") (pin "26") (pinfunction "TXD_26") (pintype "output"))
      (node (ref "R24") (pin "2") (pinfunction "2_2") (pintype "passive"))
    )
    (net (code "21") (name "Net-(IC1-VDD)") (class "Default")
      (node (ref "IC1") (pin "6") (pinfunction "VDD_6") (pintype "power_in"))
      (node (ref "R22") (pin "2") (pinfunction "2_2") (pintype "passive"))
    )
    (net (code "22") (name "Net-(IC1-~{RST})") (class "Default")
      (node (ref "IC1") (pin "9") (pinfunction "~{RST}_9") (pintype "bidirectional"))
      (node (ref "R22") (pin "1") (pinfunction "1_1") (pintype "passive"))
      (node (ref "S3") (pin "P$1") (pinfunction "P$1_P$1") (pintype "bidirectional"))
    )
    (net (code "23") (name "Net-(LED1-PadA)") (class "Default")
      (node (ref "LED1") (pin "A") (pinfunction "A_A") (pintype "passive"))
      (node (ref "R7") (pin "1") (pinfunction "1_1") (pintype "passive"))
    )
    (net (code "24") (name "Net-(LED2-PadA)") (class "Default")
      (node (ref "LED2") (pin "A") (pinfunction "A_A") (pintype "passive"))
      (node (ref "R8") (pin "1") (pinfunction "1_1") (pintype "passive"))
    )
    (net (code "25") (name "Net-(LED3-PadA)") (class "Default")
      (node (ref "LED3") (pin "A") (pinfunction "A_A") (pintype "passive"))
      (node (ref "R11") (pin "1") (pinfunction "1_1") (pintype "passive"))
    )
    (net (code "26") (name "Net-(LED4-PadA)") (class "Default")
      (node (ref "LED4") (pin "A") (pinfunction "A_A") (pintype "passive"))
      (node (ref "R12") (pin "1") (pinfunction "1_1") (pintype "passive"))
    )
    (net (code "27") (name "Net-(LED5-PadC)") (class "Default")
      (node (ref "LED5") (pin "C") (pinfunction "C_C") (pintype "passive"))
      (node (ref "R23") (pin "1") (pinfunction "1_1") (pintype "passive"))
    )
    (net (code "28") (name "Net-(LED6-PadC)") (class "Default")
      (node (ref "LED6") (pin "C") (pinfunction "C_C") (pintype "passive"))
      (node (ref "R25") (pin "1") (pinfunction "1_1") (pintype "passive"))
    )
    (net (code "29") (name "Net-(LED7-PadA)") (class "Default")
      (node (ref "LED7") (pin "A") (pinfunction "A_A") (pintype "passive"))
      (node (ref "R31") (pin "1") (pinfunction "1_1") (pintype "passive"))
    )
    (net (code "30") (name "Net-(LED8-PadA)") (class "Default")
      (node (ref "LED8") (pin "A") (pinfunction "A_A") (pintype "passive"))
      (node (ref "R32") (pin "1") (pinfunction "1_1") (pintype "passive"))
    )
    (net (code "31") (name "Net-(LED9-PadC)") (class "Default")
      (node (ref "LED9") (pin "C") (pinfunction "C_C") (pintype "passive"))
      (node (ref "R33") (pin "2") (pinfunction "2_2") (pintype "passive"))
    )
    (net (code "32") (name "Net-(LED10-PadA)") (class "Default")
      (node (ref "LED10") (pin "A") (pinfunction "A_A") (pintype "passive"))
      (node (ref "R36") (pin "1") (pinfunction "1_1") (pintype "passive"))
    )
    (net (code "33") (name "Net-(LED11-PadA)") (class "Default")
      (node (ref "LED11") (pin "A") (pinfunction "A_A") (pintype "passive"))
      (node (ref "R38") (pin "1") (pinfunction "1_1") (pintype "passive"))
    )
    (net (code "34") (name "Net-(U$2-D+)") (class "Default")
      (node (ref "R40") (pin "1") (pinfunction "1_1") (pintype "passive"))
      (node (ref "U$2") (pin "P$3") (pinfunction "D+_P$3") (pintype "bidirectional"))
    )
    (net (code "35") (name "Net-(U$2-D-)") (class "Default")
      (node (ref "R39") (pin "1") (pinfunction "1_1") (pintype "passive"))
      (node (ref "U$2") (pin "P$2") (pinfunction "D-_P$2") (pintype "bidirectional"))
    )
    (net (code "36") (name "Net-(U$2-VCC)") (class "Default")
      (node (ref "U$2") (pin "P$1") (pinfunction "VCC_P$1") (pintype "bidirectional"))
      (node (ref "U6") (pin "17") (pinfunction "VUSB_DET_17") (pintype "bidirectional"))
    )
    (net (code "37") (name "Net-(U1-D)") (class "Default")
      (node (ref "LED1") (pin "C") (pinfunction "C_C") (pintype "passive"))
      (node (ref "U1") (pin "3") (pinfunction "D_3") (pintype "bidirectional"))
    )
    (net (code "38") (name "Net-(U2-B1)") (class "Default")
      (node (ref "R17") (pin "1") (pinfunction "1_1") (pintype "passive"))
      (node (ref "U2") (pin "14") (pinfunction "B1_14") (pintype "bidirectional"))
    )
    (net (code "39") (name "Net-(U2-B2)") (class "Default")
      (node (ref "R16") (pin "1") (pinfunction "1_1") (pintype "passive"))
      (node (ref "U2") (pin "13") (pinfunction "B2_13") (pintype "bidirectional"))
    )
    (net (code "40") (name "Net-(U2-B3)") (class "Default")
      (node (ref "R15") (pin "1") (pinfunction "1_1") (pintype "passive"))
      (node (ref "U2") (pin "12") (pinfunction "B3_12") (pintype "bidirectional"))
    )
    (net (code "41") (name "Net-(U2-B4)") (class "Default")
      (node (ref "R14") (pin "1") (pinfunction "1_1") (pintype "passive"))
      (node (ref "U2") (pin "11") (pinfunction "B4_11") (pintype "bidirectional"))
    )
    (net (code "42") (name "Net-(U2-DIR1)") (class "Default")
      (node (ref "R5") (pin "1") (pinfunction "1_1") (pintype "passive"))
      (node (ref "U2") (pin "1") (pinfunction "DIR1_1") (pintype "input"))
    )
    (net (code "43") (name "Net-(U2-DIR2)") (class "Default")
      (node (ref "R2") (pin "1") (pinfunction "1_1") (pintype "passive"))
      (node (ref "U2") (pin "2") (pinfunction "DIR2_2") (pintype "input"))
    )
    (net (code "44") (name "Net-(U2-DIR3)") (class "Default")
      (node (ref "R3") (pin "2") (pinfunction "2_2") (pintype "passive"))
      (node (ref "U2") (pin "7") (pinfunction "DIR3_7") (pintype "input"))
    )
    (net (code "45") (name "Net-(U2-DIR4)") (class "Default")
      (node (ref "R6") (pin "2") (pinfunction "2_2") (pintype "passive"))
      (node (ref "U2") (pin "8") (pinfunction "DIR4_8") (pintype "input"))
    )
    (net (code "46") (name "Net-(U3-D)") (class "Default")
      (node (ref "LED2") (pin "C") (pinfunction "C_C") (pintype "passive"))
      (node (ref "U3") (pin "3") (pinfunction "D_3") (pintype "bidirectional"))
    )
    (net (code "47") (name "Net-(U4-D)") (class "Default")
      (node (ref "LED3") (pin "C") (pinfunction "C_C") (pintype "passive"))
      (node (ref "U4") (pin "3") (pinfunction "D_3") (pintype "bidirectional"))
    )
    (net (code "48") (name "Net-(U5-D)") (class "Default")
      (node (ref "LED4") (pin "C") (pinfunction "C_C") (pintype "passive"))
      (node (ref "U5") (pin "3") (pinfunction "D_3") (pintype "bidirectional"))
    )
    (net (code "49") (name "Net-(U6-ANT)") (class "Default")
      (node (ref "U6") (pin "56") (pinfunction "ANT_56") (pintype "bidirectional"))
      (node (ref "X1") (pin "3") (pinfunction "SIGNAL_3") (pintype "passive"))
    )
    (net (code "50") (name "Net-(U6-CTS)") (class "Default")
      (node (ref "R16") (pin "2") (pinfunction "2_2") (pintype "passive"))
      (node (ref "U6") (pin "11") (pinfunction "CTS_11") (pintype "bidirectional"))
    )
    (net (code "51") (name "Net-(U6-DTR)") (class "Default")
      (node (ref "R13") (pin "2") (pinfunction "2_2") (pintype "passive"))
      (node (ref "U6") (pin "9") (pinfunction "DTR_9") (pintype "bidirectional"))
    )
    (net (code "52") (name "Net-(U6-RTS)") (class "Default")
      (node (ref "R17") (pin "2") (pinfunction "2_2") (pintype "passive"))
      (node (ref "U6") (pin "10") (pinfunction "RTS_10") (pintype "bidirectional"))
    )
    (net (code "53") (name "Net-(U6-RXD)") (class "Default")
      (node (ref "R14") (pin "2") (pinfunction "2_2") (pintype "passive"))
      (node (ref "U6") (pin "13") (pinfunction "RXD_13") (pintype "bidirectional"))
    )
    (net (code "54") (name "Net-(U6-TXD)") (class "Default")
      (node (ref "R15") (pin "2") (pinfunction "2_2") (pintype "passive"))
      (node (ref "U6") (pin "12") (pinfunction "TXD_12") (pintype "bidirectional"))
    )
    (net (code "55") (name "Net-(U6-USB_D+)") (class "Default")
      (node (ref "R40") (pin "2") (pinfunction "2_2") (pintype "passive"))
      (node (ref "U6") (pin "29") (pinfunction "USB_D+_29") (pintype "bidirectional"))
    )
    (net (code "56") (name "Net-(U6-USB_D-)") (class "Default")
      (node (ref "R39") (pin "2") (pinfunction "2_2") (pintype "passive"))
      (node (ref "U6") (pin "28") (pinfunction "USB_D-_28") (pintype "bidirectional"))
    )
    (net (code "57") (name "Net-(U7-PA0)") (class "Default")
      (node (ref "R18") (pin "1") (pinfunction "1_1") (pintype "passive"))
      (node (ref "U7") (pin "6") (pinfunction "PA0_6") (pintype "bidirectional"))
    )
    (net (code "58") (name "Net-(U7-PA1)") (class "Default")
      (node (ref "R19") (pin "1") (pinfunction "1_1") (pintype "passive"))
      (node (ref "U7") (pin "7") (pinfunction "PA1_7") (pintype "bidirectional"))
    )
    (net (code "59") (name "Net-(U7-PA2)") (class "Default")
      (node (ref "R20") (pin "1") (pinfunction "1_1") (pintype "passive"))
      (node (ref "U7") (pin "8") (pinfunction "PA2_8") (pintype "bidirectional"))
    )
    (net (code "60") (name "Net-(U7-PA3)") (class "Default")
      (node (ref "R21") (pin "1") (pinfunction "1_1") (pintype "passive"))
      (node (ref "U7") (pin "9") (pinfunction "PA3_9") (pintype "bidirectional"))
    )
    (net (code "61") (name "Net-(U7-PA11)") (class "Default")
      (node (ref "R42") (pin "2") (pinfunction "2_2") (pintype "passive"))
      (node (ref "U7") (pin "21") (pinfunction "PA11_21") (pintype "bidirectional"))
    )
    (net (code "62") (name "Net-(U7-PA12)") (class "Default")
      (node (ref "R41") (pin "2") (pinfunction "2_2") (pintype "passive"))
      (node (ref "U7") (pin "22") (pinfunction "PA12_22") (pintype "bidirectional"))
    )
    (net (code "63") (name "Net-(U7-PC14-OSC32_IN)") (class "Default")
      (node (ref "U7") (pin "2") (pinfunction "PC14-OSC32_IN_2") (pintype "bidirectional"))
      (node (ref "Y1") (pin "P$2") (pinfunction "2_P$2") (pintype "passive"))
    )
    (net (code "64") (name "Net-(U7-PC15-OSC32_OUT)") (class "Default")
      (node (ref "U7") (pin "3") (pinfunction "PC15-OSC32_OUT_3") (pintype "bidirectional"))
      (node (ref "Y1") (pin "P$1") (pinfunction "1_P$1") (pintype "passive"))
    )
    (net (code "65") (name "Net-(U8-D)") (class "Default")
      (node (ref "LED7") (pin "C") (pinfunction "C_C") (pintype "passive"))
      (node (ref "U8") (pin "3") (pinfunction "D_3") (pintype "bidirectional"))
    )
    (net (code "66") (name "Net-(U9-D)") (class "Default")
      (node (ref "LED8") (pin "C") (pinfunction "C_C") (pintype "passive"))
      (node (ref "U9") (pin "3") (pinfunction "D_3") (pintype "bidirectional"))
    )
    (net (code "67") (name "Net-(U11-PROG)") (class "Default")
      (node (ref "R34") (pin "2") (pinfunction "2_2") (pintype "passive"))
      (node (ref "U11") (pin "5") (pinfunction "PROG_5") (pintype "bidirectional"))
    )
    (net (code "68") (name "Net-(U11-STAT)") (class "Default")
      (node (ref "R33") (pin "1") (pinfunction "1_1") (pintype "passive"))
      (node (ref "U11") (pin "1") (pinfunction "STAT_1") (pintype "bidirectional"))
    )
    (net (code "69") (name "Net-(U13-D)") (class "Default")
      (node (ref "LED10") (pin "C") (pinfunction "C_C") (pintype "passive"))
      (node (ref "U13") (pin "3") (pinfunction "D_3") (pintype "bidirectional"))
    )
    (net (code "70") (name "Net-(U14-D)") (class "Default")
      (node (ref "LED11") (pin "C") (pinfunction "C_C") (pintype "passive"))
      (node (ref "U14") (pin "3") (pinfunction "D_3") (pintype "bidirectional"))
    )
    (net (code "71") (name "POWER_IN") (class "Default")
      (node (ref "C15") (pin "1") (pinfunction "1_1") (pintype "passive"))
      (node (ref "C18") (pin "1") (pinfunction "1_1") (pintype "passive"))
      (node (ref "C19") (pin "1") (pinfunction "1_1") (pintype "passive"))
      (node (ref "CN1") (pin "1") (pinfunction "2_1") (pintype "passive"))
      (node (ref "J3") (pin "2") (pinfunction "2_2") (pintype "passive"))
      (node (ref "R31") (pin "2") (pinfunction "2_2") (pintype "passive"))
      (node (ref "R32") (pin "2") (pinfunction "2_2") (pintype "passive"))
      (node (ref "U10") (pin "1") (pinfunction "IN_1") (pintype "bidirectional"))
      (node (ref "U10") (pin "3") (pinfunction "EN_3") (pintype "bidirectional"))
      (node (ref "U11") (pin "3") (pinfunction "VBAT_3") (pintype "bidirectional"))
      (node (ref "U12") (pin "1") (pinfunction "VIN_1") (pintype "bidirectional"))
    )
    (net (code "72") (name "POWER_ON") (class "Default")
      (node (ref "S2") (pin "P$1") (pinfunction "P$1_P$1") (pintype "bidirectional"))
      (node (ref "U6") (pin "15") (pinfunction "PWR_ON_15") (pintype "bidirectional"))
      (node (ref "U7") (pin "10") (pinfunction "PA4_10") (pintype "bidirectional"))
    )
    (net (code "73") (name "R404M_RESET") (class "Default")
      (node (ref "S1") (pin "P$1") (pinfunction "P$1_P$1") (pintype "bidirectional"))
      (node (ref "U6") (pin "18") (pinfunction "RESET_N_18") (pintype "bidirectional"))
      (node (ref "U7") (pin "12") (pinfunction "PA6_12") (pintype "bidirectional"))
    )
    (net (code "74") (name "SIM_CLK") (class "Default")
      (node (ref "C10") (pin "1") (pinfunction "1_1") (pintype "passive"))
      (node (ref "U$1") (pin "C3") (pinfunction "SIMCLK_C3") (pintype "bidirectional"))
      (node (ref "U6") (pin "38") (pinfunction "SIM_CLK_38") (pintype "bidirectional"))
    )
    (net (code "75") (name "SIM_IO") (class "Default")
      (node (ref "C11") (pin "1") (pinfunction "1_1") (pintype "passive"))
      (node (ref "U$1") (pin "C7") (pinfunction "IO_C7") (pintype "bidirectional"))
      (node (ref "U6") (pin "39") (pinfunction "SIM_IO_39") (pintype "bidirectional"))
    )
    (net (code "76") (name "SIM_RST") (class "Default")
      (node (ref "C8") (pin "1") (pinfunction "1_1") (pintype "passive"))
      (node (ref "U$1") (pin "C2") (pinfunction "RST_C2") (pintype "bidirectional"))
      (node (ref "U6") (pin "40") (pinfunction "SIM_RST_40") (pintype "bidirectional"))
    )
    (net (code "77") (name "SWCLK") (class "Default")
      (node (ref "J1") (pin "2") (pinfunction "2_2") (pintype "passive"))
      (node (ref "U7") (pin "24") (pinfunction "PA14_24") (pintype "bidirectional"))
    )
    (net (code "78") (name "SWDIO") (class "Default")
      (node (ref "J1") (pin "3") (pinfunction "3_3") (pintype "passive"))
      (node (ref "U7") (pin "23") (pinfunction "PA13_23") (pintype "bidirectional"))
    )
    (net (code "79") (name "UART_CTS") (class "Default")
      (node (ref "R18") (pin "2") (pinfunction "2_2") (pintype "passive"))
      (node (ref "R28") (pin "1") (pinfunction "1_1") (pintype "passive"))
      (node (ref "U2") (pin "4") (pinfunction "A2_4") (pintype "bidirectional"))
    )
    (net (code "80") (name "UART_RTS") (class "Default")
      (node (ref "R19") (pin "2") (pinfunction "2_2") (pintype "passive"))
      (node (ref "R27") (pin "1") (pinfunction "1_1") (pintype "passive"))
      (node (ref "U2") (pin "3") (pinfunction "A1_3") (pintype "bidirectional"))
    )
    (net (code "81") (name "UART_RXD") (class "Default")
      (node (ref "R21") (pin "2") (pinfunction "2_2") (pintype "passive"))
      (node (ref "R26") (pin "1") (pinfunction "1_1") (pintype "passive"))
      (node (ref "U2") (pin "6") (pinfunction "A4_6") (pintype "bidirectional"))
    )
    (net (code "82") (name "UART_TXD") (class "Default")
      (node (ref "R20") (pin "2") (pinfunction "2_2") (pintype "passive"))
      (node (ref "R24") (pin "1") (pinfunction "1_1") (pintype "passive"))
      (node (ref "U2") (pin "5") (pinfunction "A3_5") (pintype "bidirectional"))
    )
    (net (code "83") (name "USB_DM") (class "Default")
      (node (ref "R42") (pin "1") (pinfunction "1_1") (pintype "passive"))
      (node (ref "U$4") (pin "P$2") (pinfunction "D-_P$2") (pintype "bidirectional"))
    )
    (net (code "84") (name "USB_DP") (class "Default")
      (node (ref "R41") (pin "1") (pinfunction "1_1") (pintype "passive"))
      (node (ref "U$4") (pin "P$3") (pinfunction "D+_P$3") (pintype "bidirectional"))
    )
    (net (code "85") (name "VBUS") (class "Default")
      (node (ref "C12") (pin "1") (pinfunction "1_1") (pintype "passive"))
      (node (ref "C16") (pin "1") (pinfunction "1_1") (pintype "passive"))
      (node (ref "IC1") (pin "7") (pinfunction "REGIN_7") (pintype "passive"))
      (node (ref "IC1") (pin "8") (pinfunction "VBUS_8") (pintype "input"))
      (node (ref "LED9") (pin "A") (pinfunction "A_A") (pintype "passive"))
      (node (ref "U$3") (pin "P$1") (pinfunction "VCC_P$1") (pintype "bidirectional"))
      (node (ref "U11") (pin "4") (pinfunction "VIN_4") (pintype "bidirectional"))
    )
    (net (code "86") (name "VIN") (class "Default")
      (node (ref "U$4") (pin "P$1") (pinfunction "VCC_P$1") (pintype "bidirectional"))
    )
    (net (code "87") (name "VSIM") (class "Default")
      (node (ref "C7") (pin "1") (pinfunction "1_1") (pintype "passive"))
      (node (ref "C9") (pin "1") (pinfunction "1_1") (pintype "passive"))
      (node (ref "U$1") (pin "C1") (pinfunction "VCC_C1") (pintype "bidirectional"))
      (node (ref "U6") (pin "41") (pinfunction "VSIM_41") (pintype "bidirectional"))
    )
    (net (code "88") (name "V_INT") (class "Default")
      (node (ref "C1") (pin "1") (pinfunction "1_1") (pintype "passive"))
      (node (ref "U2") (pin "15") (pinfunction "VCCB_15") (pintype "power_in"))
      (node (ref "U6") (pin "4") (pinfunction "V_INT_4") (pintype "bidirectional"))
    )
    (net (code "89") (name "unconnected-(IC1-CHR0-Pad15)") (class "Default")
      (node (ref "IC1") (pin "15") (pinfunction "CHR0_15") (pintype "bidirectional"))
    )
    (net (code "90") (name "unconnected-(IC1-CHR1-Pad14)") (class "Default")
      (node (ref "IC1") (pin "14") (pinfunction "CHR1_14") (pintype "bidirectional"))
    )
    (net (code "91") (name "unconnected-(IC1-CHREN-Pad13)") (class "Default")
      (node (ref "IC1") (pin "13") (pinfunction "CHREN_13") (pintype "bidirectional"))
    )
    (net (code "92") (name "unconnected-(IC1-DCD-Pad1)") (class "Default")
      (node (ref "IC1") (pin "1") (pinfunction "DCD_1") (pintype "input"))
    )
    (net (code "93") (name "unconnected-(IC1-DSR-Pad27)") (class "Default")
      (node (ref "IC1") (pin "27") (pinfunction "DSR_27") (pintype "input"))
    )
    (net (code "94") (name "unconnected-(IC1-DTR-Pad28)") (class "Default")
      (node (ref "IC1") (pin "28") (pinfunction "DTR_28") (pintype "output"))
    )
    (net (code "95") (name "unconnected-(IC1-GPIO2-Pad17)") (class "Default")
      (node (ref "IC1") (pin "17") (pinfunction "GPIO2_17") (pintype "bidirectional"))
    )
    (net (code "96") (name "unconnected-(IC1-GPIO3-Pad16)") (class "Default")
      (node (ref "IC1") (pin "16") (pinfunction "GPIO3_16") (pintype "bidirectional"))
    )
    (net (code "97") (name "unconnected-(IC1-GPIO4-Pad22)") (class "Default")
      (node (ref "IC1") (pin "22") (pinfunction "GPIO4_22") (pintype "bidirectional"))
    )
    (net (code "98") (name "unconnected-(IC1-GPIO5-Pad21)") (class "Default")
      (node (ref "IC1") (pin "21") (pinfunction "GPIO5_21") (pintype "bidirectional"))
    )
    (net (code "99") (name "unconnected-(IC1-GPIO6-Pad20)") (class "Default")
      (node (ref "IC1") (pin "20") (pinfunction "GPIO6_20") (pintype "bidirectional"))
    )
    (net (code "100") (name "unconnected-(IC1-RI-Pad2)") (class "Default")
      (node (ref "IC1") (pin "2") (pinfunction "RI_2") (pintype "input"))
    )
    (net (code "101") (name "unconnected-(IC1-SUSPEND-Pad12)") (class "Default")
      (node (ref "IC1") (pin "12") (pinfunction "SUSPEND_12") (pintype "output"))
    )
    (net (code "102") (name "unconnected-(IC1-~{SUSPEND}-Pad11)") (class "Default")
      (node (ref "IC1") (pin "11") (pinfunction "~{SUSPEND}_11") (pintype "output"))
    )
    (net (code "103") (name "unconnected-(S1-PadP$2)") (class "Default")
      (node (ref "S1") (pin "P$2") (pinfunction "P$2_P$2") (pintype "bidirectional"))
    )
    (net (code "104") (name "unconnected-(S1-PadP$3)") (class "Default")
      (node (ref "S1") (pin "P$3") (pinfunction "P$3_P$3") (pintype "bidirectional"))
    )
    (net (code "105") (name "unconnected-(S2-PadP$2)") (class "Default")
      (node (ref "S2") (pin "P$2") (pinfunction "P$2_P$2") (pintype "bidirectional"))
    )
    (net (code "106") (name "unconnected-(S2-PadP$4)") (class "Default")
      (node (ref "S2") (pin "P$4") (pinfunction "P$4_P$4") (pintype "bidirectional"))
    )
    (net (code "107") (name "unconnected-(S3-PadP$2)") (class "Default")
      (node (ref "S3") (pin "P$2") (pinfunction "P$2_P$2") (pintype "bidirectional"))
    )
    (net (code "108") (name "unconnected-(S3-PadP$3)") (class "Default")
      (node (ref "S3") (pin "P$3") (pinfunction "P$3_P$3") (pintype "bidirectional"))
    )
    (net (code "109") (name "unconnected-(S4-PadP$2)") (class "Default")
      (node (ref "S4") (pin "P$2") (pinfunction "P$2_P$2") (pintype "bidirectional"))
    )
    (net (code "110") (name "unconnected-(S4-PadP$3)") (class "Default")
      (node (ref "S4") (pin "P$3") (pinfunction "P$3_P$3") (pintype "bidirectional"))
    )
    (net (code "111") (name "unconnected-(U$1-CD{slash}DAT3-PadT2)") (class "Default")
      (node (ref "U$1") (pin "T2") (pinfunction "CD/DAT3_T2") (pintype "bidirectional"))
    )
    (net (code "112") (name "unconnected-(U$1-CMD-PadT3)") (class "Default")
      (node (ref "U$1") (pin "T3") (pinfunction "CMD_T3") (pintype "bidirectional"))
    )
    (net (code "113") (name "unconnected-(U$1-DAT0-PadT7)") (class "Default")
      (node (ref "U$1") (pin "T7") (pinfunction "DAT0_T7") (pintype "bidirectional"))
    )
    (net (code "114") (name "unconnected-(U$1-DAT1-PadT8)") (class "Default")
      (node (ref "U$1") (pin "T8") (pinfunction "DAT1_T8") (pintype "bidirectional"))
    )
    (net (code "115") (name "unconnected-(U$1-DAT2-PadT1)") (class "Default")
      (node (ref "U$1") (pin "T1") (pinfunction "DAT2_T1") (pintype "bidirectional"))
    )
    (net (code "116") (name "unconnected-(U$1-SDCLK-PadT5)") (class "Default")
      (node (ref "U$1") (pin "T5") (pinfunction "SDCLK_T5") (pintype "bidirectional"))
    )
    (net (code "117") (name "unconnected-(U$1-SD_DET-PadSW)") (class "Default")
      (node (ref "U$1") (pin "SW") (pinfunction "SD_DET_SW") (pintype "bidirectional"))
    )
    (net (code "118") (name "unconnected-(U$1-VDD-PadT4)") (class "Default")
      (node (ref "U$1") (pin "T4") (pinfunction "VDD_T4") (pintype "bidirectional"))
    )
    (net (code "119") (name "unconnected-(U$1-VPP-PadC6)") (class "Default")
      (node (ref "U$1") (pin "C6") (pinfunction "VPP_C6") (pintype "bidirectional"))
    )
    (net (code "120") (name "unconnected-(U$2-ID-PadP$4)") (class "Default")
      (node (ref "U$2") (pin "P$4") (pinfunction "ID_P$4") (pintype "bidirectional"))
    )
    (net (code "121") (name "unconnected-(U$3-ID-PadP$4)") (class "Default")
      (node (ref "U$3") (pin "P$4") (pinfunction "ID_P$4") (pintype "bidirectional"))
    )
    (net (code "122") (name "unconnected-(U$4-ID-PadP$4)") (class "Default")
      (node (ref "U$4") (pin "P$4") (pinfunction "ID_P$4") (pintype "bidirectional"))
    )
    (net (code "123") (name "unconnected-(U6-ANT_DET-Pad62)") (class "Default")
      (node (ref "U6") (pin "62") (pinfunction "ANT_DET_62") (pintype "bidirectional"))
    )
    (net (code "124") (name "unconnected-(U6-DCD-Pad8)") (class "Default")
      (node (ref "U6") (pin "8") (pinfunction "DCD_8") (pintype "bidirectional"))
    )
    (net (code "125") (name "unconnected-(U6-DSR-Pad6)") (class "Default")
      (node (ref "U6") (pin "6") (pinfunction "DSR_6") (pintype "bidirectional"))
    )
    (net (code "126") (name "unconnected-(U6-I2S_CLK{slash}CLK-Pad36)") (class "Default")
      (node (ref "U6") (pin "36") (pinfunction "I2S_CLK/CLK_36") (pintype "bidirectional"))
    )
    (net (code "127") (name "unconnected-(U6-I2S_RXD{slash}MISO-Pad37)") (class "Default")
      (node (ref "U6") (pin "37") (pinfunction "I2S_RXD/MISO_37") (pintype "bidirectional"))
    )
    (net (code "128") (name "unconnected-(U6-I2S_TXD{slash}CS-Pad35)") (class "Default")
      (node (ref "U6") (pin "35") (pinfunction "I2S_TXD/CS_35") (pintype "bidirectional"))
    )
    (net (code "129") (name "unconnected-(U6-I2S_WA{slash}MOSI-Pad34)") (class "Default")
      (node (ref "U6") (pin "34") (pinfunction "I2S_WA/MOSI_34") (pintype "bidirectional"))
    )
    (net (code "130") (name "unconnected-(U6-RI-Pad7)") (class "Default")
      (node (ref "U6") (pin "7") (pinfunction "RI_7") (pintype "bidirectional"))
    )
    (net (code "131") (name "unconnected-(U6-SCL-Pad27)") (class "Default")
      (node (ref "U6") (pin "27") (pinfunction "SCL_27") (pintype "bidirectional"))
    )
    (net (code "132") (name "unconnected-(U6-SDA-Pad26)") (class "Default")
      (node (ref "U6") (pin "26") (pinfunction "SDA_26") (pintype "bidirectional"))
    )
    (net (code "133") (name "unconnected-(U6-SDIO_CLK-Pad45)") (class "Default")
      (node (ref "U6") (pin "45") (pinfunction "SDIO_CLK_45") (pintype "bidirectional"))
    )
    (net (code "134") (name "unconnected-(U6-SDIO_CMD-Pad46)") (class "Default")
      (node (ref "U6") (pin "46") (pinfunction "SDIO_CMD_46") (pintype "bidirectional"))
    )
    (net (code "135") (name "unconnected-(U6-SDIO_D0-Pad47)") (class "Default")
      (node (ref "U6") (pin "47") (pinfunction "SDIO_D0_47") (pintype "bidirectional"))
    )
    (net (code "136") (name "unconnected-(U6-SDIO_D1-Pad49)") (class "Default")
      (node (ref "U6") (pin "49") (pinfunction "SDIO_D1_49") (pintype "bidirectional"))
    )
    (net (code "137") (name "unconnected-(U6-SDIO_D2-Pad44)") (class "Default")
      (node (ref "U6") (pin "44") (pinfunction "SDIO_D2_44") (pintype "bidirectional"))
    )
    (net (code "138") (name "unconnected-(U6-SDIO_D3-Pad48)") (class "Default")
      (node (ref "U6") (pin "48") (pinfunction "SDIO_D3_48") (pintype "bidirectional"))
    )
    (net (code "139") (name "unconnected-(U7-BOOT0-Pad31)") (class "Default")
      (node (ref "U7") (pin "31") (pinfunction "BOOT0_31") (pintype "bidirectional"))
    )
    (net (code "140") (name "unconnected-(U7-PA7-Pad13)") (class "Default")
      (node (ref "U7") (pin "13") (pinfunction "PA7_13") (pintype "bidirectional"))
    )
    (net (code "141") (name "unconnected-(U7-PA8-Pad18)") (class "Default")
      (node (ref "U7") (pin "18") (pinfunction "PA8_18") (pintype "bidirectional"))
    )
    (net (code "142") (name "unconnected-(U7-PA9-Pad19)") (class "Default")
      (node (ref "U7") (pin "19") (pinfunction "PA9_19") (pintype "bidirectional"))
    )
    (net (code "143") (name "unconnected-(U7-PA10-Pad20)") (class "Default")
      (node (ref "U7") (pin "20") (pinfunction "PA10_20") (pintype "bidirectional"))
    )
    (net (code "144") (name "unconnected-(U7-PA15-Pad25)") (class "Default")
      (node (ref "U7") (pin "25") (pinfunction "PA15_25") (pintype "bidirectional"))
    )
    (net (code "145") (name "unconnected-(U7-PB0-Pad14)") (class "Default")
      (node (ref "U7") (pin "14") (pinfunction "PB0_14") (pintype "bidirectional"))
    )
    (net (code "146") (name "unconnected-(U7-PB1-Pad15)") (class "Default")
      (node (ref "U7") (pin "15") (pinfunction "PB1_15") (pintype "bidirectional"))
    )
    (net (code "147") (name "unconnected-(U7-PB3-Pad26)") (class "Default")
      (node (ref "U7") (pin "26") (pinfunction "PB3_26") (pintype "bidirectional"))
    )
    (net (code "148") (name "unconnected-(U7-PB4-Pad27)") (class "Default")
      (node (ref "U7") (pin "27") (pinfunction "PB4_27") (pintype "bidirectional"))
    )
    (net (code "149") (name "unconnected-(U7-PB5-Pad28)") (class "Default")
      (node (ref "U7") (pin "28") (pinfunction "PB5_28") (pintype "bidirectional"))
    )
    (net (code "150") (name "unconnected-(U12-CT-Pad4)") (class "Default")
      (node (ref "U12") (pin "4") (pinfunction "CT_4") (pintype "bidirectional"))
    )
    (net (code "151") (name "unconnected-(U12-QOD-Pad5)") (class "Default")
      (node (ref "U12") (pin "5") (pinfunction "QOD_5") (pintype "bidirectional"))
    )
    (net (code "152") (name "~{RST}") (class "Default")
      (node (ref "J1") (pin "4") (pinfunction "4_4") (pintype "passive"))
      (node (ref "S4") (pin "P$1") (pinfunction "P$1_P$1") (pintype "bidirectional"))
      (node (ref "U7") (pin "4") (pinfunction "NRST_4") (pintype "bidirectional"))
    )
  )
)
